# PCA9306.net
KiCad netlist of a schematic drawn in EAGLE
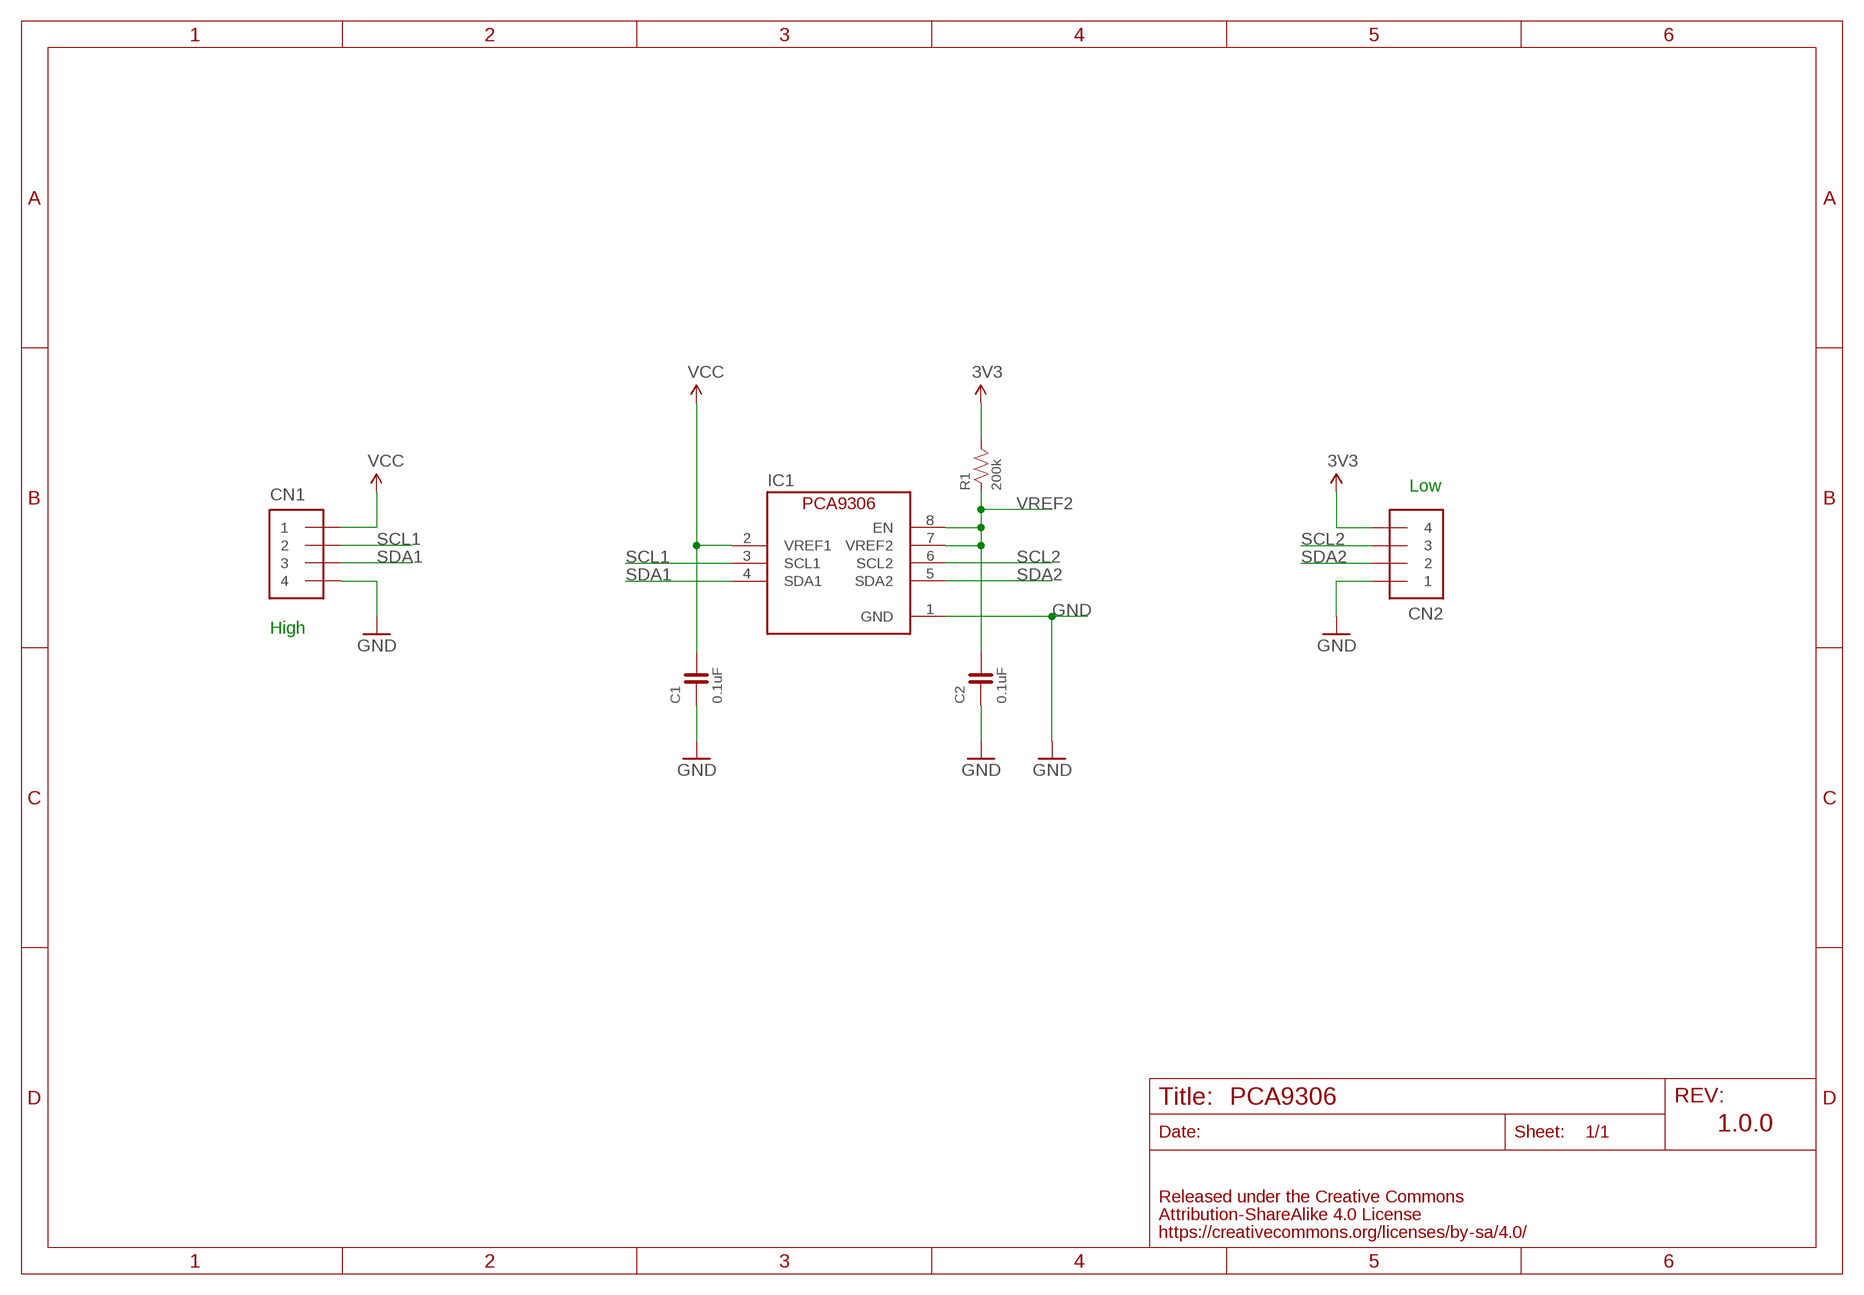
[diagram p0: schematic, sheet 1]

(export (version "E")
  (design (tool "Eeschema 10.0.6"))
  (components
    (comp (ref "C1")
      (value "0.1uF")
      (footprint "eagle-import:0603")
      (libsource (lib "eagle-import") (part "CAPACITOR-0603"))
    )
    (comp (ref "C2")
      (value "0.1uF")
      (footprint "eagle-import:0603")
      (libsource (lib "eagle-import") (part "CAPACITOR-0603"))
    )
    (comp (ref "CN1")
      (value "PIN_HEADER_1X4")
      (footprint "eagle-import:PIN_1X4_SNEAKY")
      (libsource (lib "eagle-import") (part "PIN_HEADER_1X4"))
    )
    (comp (ref "CN2")
      (value "PIN_HEADER_1X4")
      (footprint "eagle-import:PIN_1X4_SNEAKY")
      (libsource (lib "eagle-import") (part "PIN_HEADER_1X4"))
    )
    (comp (ref "IC1")
      (value "TI-PCA9306DQE")
      (footprint "eagle-import:TI-PCA9306")
      (libsource (lib "eagle-import") (part "TI-PCA9306DQE"))
    )
    (comp (ref "R1")
      (value "200k")
      (footprint "eagle-import:0603")
      (libsource (lib "eagle-import") (part "RESISTOR-0603"))
    )
  )
  (nets
    (net (code "1") (name "/SCL1") (class "Default")
      (node (ref "CN1") (pin "2") (pinfunction "2_2") (pintype "bidirectional"))
      (node (ref "IC1") (pin "3") (pinfunction "SCL1_3") (pintype "bidirectional"))
    )
    (net (code "2") (name "/SCL2") (class "Default")
      (node (ref "CN2") (pin "3") (pinfunction "3_3") (pintype "bidirectional"))
      (node (ref "IC1") (pin "6") (pinfunction "SCL2_6") (pintype "bidirectional"))
    )
    (net (code "3") (name "/SDA1") (class "Default")
      (node (ref "CN1") (pin "3") (pinfunction "3_3") (pintype "bidirectional"))
      (node (ref "IC1") (pin "4") (pinfunction "SDA1_4") (pintype "bidirectional"))
    )
    (net (code "4") (name "/SDA2") (class "Default")
      (node (ref "CN2") (pin "2") (pinfunction "2_2") (pintype "bidirectional"))
      (node (ref "IC1") (pin "5") (pinfunction "SDA2_5") (pintype "bidirectional"))
    )
    (net (code "5") (name "/VREF2") (class "Default")
      (node (ref "C2") (pin "2") (pinfunction "2_2") (pintype "passive"))
      (node (ref "IC1") (pin "7") (pinfunction "VREF2_7") (pintype "bidirectional"))
      (node (ref "IC1") (pin "8") (pinfunction "EN_8") (pintype "bidirectional"))
      (node (ref "R1") (pin "1") (pinfunction "1_1") (pintype "bidirectional"))
    )
    (net (code "6") (name "3V3") (class "Default")
      (node (ref "CN2") (pin "4") (pinfunction "4_4") (pintype "bidirectional"))
      (node (ref "R1") (pin "2") (pinfunction "2_2") (pintype "bidirectional"))
    )
    (net (code "7") (name "GND") (class "Default")
      (node (ref "C1") (pin "1") (pinfunction "1_1") (pintype "passive"))
      (node (ref "C2") (pin "1") (pinfunction "1_1") (pintype "passive"))
      (node (ref "CN1") (pin "4") (pinfunction "4_4") (pintype "bidirectional"))
      (node (ref "CN2") (pin "1") (pinfunction "1_1") (pintype "bidirectional"))
      (node (ref "IC1") (pin "1") (pinfunction "GND_1") (pintype "bidirectional"))
    )
    (net (code "8") (name "VCC") (class "Default")
      (node (ref "C1") (pin "2") (pinfunction "2_2") (pintype "passive"))
      (node (ref "CN1") (pin "1") (pinfunction "1_1") (pintype "bidirectional"))
      (node (ref "IC1") (pin "2") (pinfunction "VREF1_2") (pintype "bidirectional"))
    )
  )
)
